# R2R_v2_1.net
KiCad netlist of a schematic drawn in EAGLE
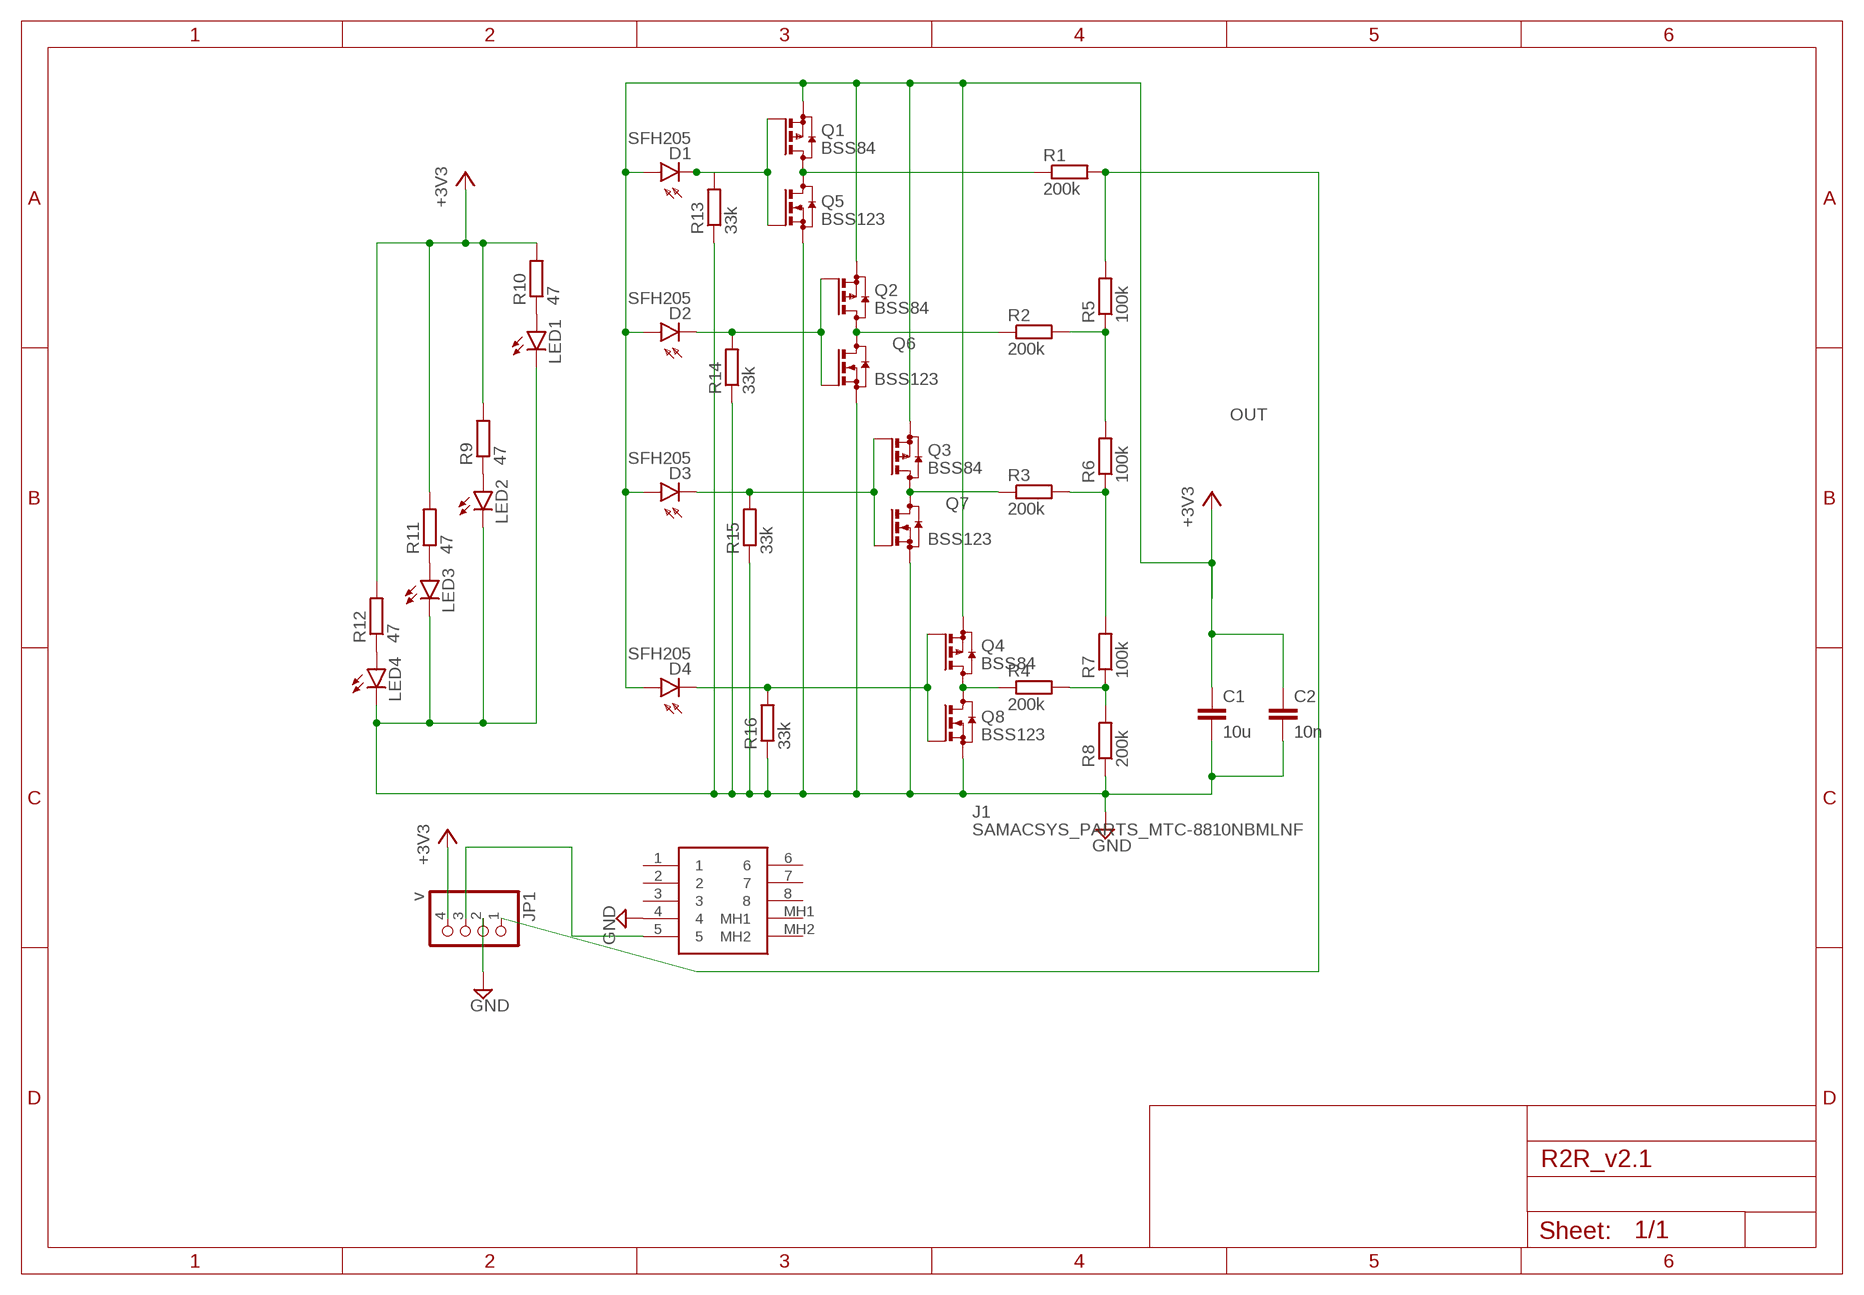
[diagram p0: schematic, sheet 1]

(export (version "E")
  (design (tool "Eeschema 10.0.6"))
  (components
    (comp (ref "C1")
      (value "10u")
      (footprint "eagle-import:C0805")
      (libsource (lib "eagle-import") (part "C-EUC0805"))
    )
    (comp (ref "C2")
      (value "10n")
      (footprint "eagle-import:C0805")
      (libsource (lib "eagle-import") (part "C-EUC0805"))
    )
    (comp (ref "D1")
      (value "SFH205")
      (footprint "eagle-import:SFH205")
      (libsource (lib "eagle-import") (part "SFH205"))
    )
    (comp (ref "D2")
      (value "SFH205")
      (footprint "eagle-import:SFH205")
      (libsource (lib "eagle-import") (part "SFH205"))
    )
    (comp (ref "D3")
      (value "SFH205")
      (footprint "eagle-import:SFH205")
      (libsource (lib "eagle-import") (part "SFH205"))
    )
    (comp (ref "D4")
      (value "SFH205")
      (footprint "eagle-import:SFH205")
      (libsource (lib "eagle-import") (part "SFH205"))
    )
    (comp (ref "J1")
      (value "SAMACSYS_PARTS_MTC-8810NBMLNF")
      (footprint "eagle-import:SAMACSYS_PARTS_MTC8810NBMLNF")
      (fields (field (name "MANUFACTURER_PART_NUMBER") "MTC-8810NBMLNF"))
      (libsource (lib "eagle-import") (part "SAMACSYS_PARTS_MTC-8810NBMLNF"))
    )
    (comp (ref "JP1")
      (value "v")
      (footprint "eagle-import:1X04")
      (libsource (lib "eagle-import") (part "PINHD-1X4"))
    )
    (comp (ref "LED1")
      (value "LED3MM")
      (footprint "eagle-import:LED3MM")
      (libsource (lib "eagle-import") (part "LED3MM"))
    )
    (comp (ref "LED2")
      (value "LED3MM")
      (footprint "eagle-import:LED3MM")
      (libsource (lib "eagle-import") (part "LED3MM"))
    )
    (comp (ref "LED3")
      (value "LED3MM")
      (footprint "eagle-import:LED3MM")
      (libsource (lib "eagle-import") (part "LED3MM"))
    )
    (comp (ref "LED4")
      (value "LED3MM")
      (footprint "eagle-import:LED3MM")
      (libsource (lib "eagle-import") (part "LED3MM"))
    )
    (comp (ref "Q1")
      (value "BSS84")
      (footprint "eagle-import:SOT23")
      (libsource (lib "eagle-import") (part "BSS84"))
    )
    (comp (ref "Q2")
      (value "BSS84")
      (footprint "eagle-import:SOT23")
      (libsource (lib "eagle-import") (part "BSS84"))
    )
    (comp (ref "Q3")
      (value "BSS84")
      (footprint "eagle-import:SOT23")
      (libsource (lib "eagle-import") (part "BSS84"))
    )
    (comp (ref "Q4")
      (value "BSS84")
      (footprint "eagle-import:SOT23")
      (libsource (lib "eagle-import") (part "BSS84"))
    )
    (comp (ref "Q5")
      (value "BSS123")
      (footprint "eagle-import:SOT23")
      (libsource (lib "eagle-import") (part "BSS123"))
    )
    (comp (ref "Q6")
      (value "BSS123")
      (footprint "eagle-import:SOT23")
      (libsource (lib "eagle-import") (part "BSS123"))
    )
    (comp (ref "Q7")
      (value "BSS123")
      (footprint "eagle-import:SOT23")
      (libsource (lib "eagle-import") (part "BSS123"))
    )
    (comp (ref "Q8")
      (value "BSS123")
      (footprint "eagle-import:SOT23")
      (libsource (lib "eagle-import") (part "BSS123"))
    )
    (comp (ref "R1")
      (value "200k")
      (footprint "eagle-import:R1206")
      (libsource (lib "eagle-import") (part "R-EU_R1206"))
    )
    (comp (ref "R2")
      (value "200k")
      (footprint "eagle-import:R1206")
      (libsource (lib "eagle-import") (part "R-EU_R1206"))
    )
    (comp (ref "R3")
      (value "200k")
      (footprint "eagle-import:R1206")
      (libsource (lib "eagle-import") (part "R-EU_R1206"))
    )
    (comp (ref "R4")
      (value "200k")
      (footprint "eagle-import:R1206")
      (libsource (lib "eagle-import") (part "R-EU_R1206"))
    )
    (comp (ref "R5")
      (value "100k")
      (footprint "eagle-import:R1206")
      (libsource (lib "eagle-import") (part "R-EU_R1206"))
    )
    (comp (ref "R6")
      (value "100k")
      (footprint "eagle-import:R1206")
      (libsource (lib "eagle-import") (part "R-EU_R1206"))
    )
    (comp (ref "R7")
      (value "100k")
      (footprint "eagle-import:R1206")
      (libsource (lib "eagle-import") (part "R-EU_R1206"))
    )
    (comp (ref "R8")
      (value "200k")
      (footprint "eagle-import:R1206")
      (libsource (lib "eagle-import") (part "R-EU_R1206"))
    )
    (comp (ref "R9")
      (value "47")
      (footprint "eagle-import:R1206")
      (libsource (lib "eagle-import") (part "R-EU_R1206"))
    )
    (comp (ref "R10")
      (value "47")
      (footprint "eagle-import:R1206")
      (libsource (lib "eagle-import") (part "R-EU_R1206"))
    )
    (comp (ref "R11")
      (value "47")
      (footprint "eagle-import:R1206")
      (libsource (lib "eagle-import") (part "R-EU_R1206"))
    )
    (comp (ref "R12")
      (value "47")
      (footprint "eagle-import:R1206")
      (libsource (lib "eagle-import") (part "R-EU_R1206"))
    )
    (comp (ref "R13")
      (value "33k")
      (footprint "eagle-import:R1206")
      (libsource (lib "eagle-import") (part "R-EU_R1206"))
    )
    (comp (ref "R14")
      (value "33k")
      (footprint "eagle-import:R1206")
      (libsource (lib "eagle-import") (part "R-EU_R1206"))
    )
    (comp (ref "R15")
      (value "33k")
      (footprint "eagle-import:R1206")
      (libsource (lib "eagle-import") (part "R-EU_R1206"))
    )
    (comp (ref "R16")
      (value "33k")
      (footprint "eagle-import:R1206")
      (libsource (lib "eagle-import") (part "R-EU_R1206"))
    )
  )
  (nets
    (net (code "1") (name "+3V3") (class "Default")
      (node (ref "C1") (pin "1") (pinfunction "1_1") (pintype "passive"))
      (node (ref "C2") (pin "1") (pinfunction "1_1") (pintype "passive"))
      (node (ref "D1") (pin "A") (pinfunction "A_A") (pintype "passive"))
      (node (ref "D2") (pin "A") (pinfunction "A_A") (pintype "passive"))
      (node (ref "D3") (pin "A") (pinfunction "A_A") (pintype "passive"))
      (node (ref "D4") (pin "A") (pinfunction "A_A") (pintype "passive"))
      (node (ref "JP1") (pin "4") (pinfunction "4_4") (pintype "passive"))
      (node (ref "Q1") (pin "2") (pinfunction "S_2") (pintype "passive"))
      (node (ref "Q2") (pin "2") (pinfunction "S_2") (pintype "passive"))
      (node (ref "Q3") (pin "2") (pinfunction "S_2") (pintype "passive"))
      (node (ref "Q4") (pin "2") (pinfunction "S_2") (pintype "passive"))
      (node (ref "R10") (pin "2") (pinfunction "2_2") (pintype "passive"))
      (node (ref "R11") (pin "2") (pinfunction "2_2") (pintype "passive"))
      (node (ref "R12") (pin "2") (pinfunction "2_2") (pintype "passive"))
      (node (ref "R9") (pin "2") (pinfunction "2_2") (pintype "passive"))
    )
    (net (code "2") (name "/OUT") (class "Default")
      (node (ref "JP1") (pin "1") (pinfunction "1_1") (pintype "passive"))
      (node (ref "R1") (pin "2") (pinfunction "2_2") (pintype "passive"))
      (node (ref "R5") (pin "2") (pinfunction "2_2") (pintype "passive"))
    )
    (net (code "3") (name "GND") (class "Default")
      (node (ref "C1") (pin "2") (pinfunction "2_2") (pintype "passive"))
      (node (ref "C2") (pin "2") (pinfunction "2_2") (pintype "passive"))
      (node (ref "J1") (pin "4") (pinfunction "4_4") (pintype "bidirectional"))
      (node (ref "JP1") (pin "2") (pinfunction "2_2") (pintype "passive"))
      (node (ref "LED1") (pin "K") (pinfunction "C_K") (pintype "passive"))
      (node (ref "LED2") (pin "K") (pinfunction "C_K") (pintype "passive"))
      (node (ref "LED3") (pin "K") (pinfunction "C_K") (pintype "passive"))
      (node (ref "LED4") (pin "K") (pinfunction "C_K") (pintype "passive"))
      (node (ref "Q5") (pin "2") (pinfunction "S_2") (pintype "passive"))
      (node (ref "Q6") (pin "2") (pinfunction "S_2") (pintype "passive"))
      (node (ref "Q7") (pin "2") (pinfunction "S_2") (pintype "passive"))
      (node (ref "Q8") (pin "2") (pinfunction "S_2") (pintype "passive"))
      (node (ref "R13") (pin "1") (pinfunction "1_1") (pintype "passive"))
      (node (ref "R14") (pin "1") (pinfunction "1_1") (pintype "passive"))
      (node (ref "R15") (pin "1") (pinfunction "1_1") (pintype "passive"))
      (node (ref "R16") (pin "1") (pinfunction "1_1") (pintype "passive"))
      (node (ref "R8") (pin "1") (pinfunction "1_1") (pintype "passive"))
    )
    (net (code "4") (name "Net-(D1-C)") (class "Default")
      (node (ref "D1") (pin "K") (pinfunction "C_K") (pintype "passive"))
      (node (ref "Q1") (pin "1") (pinfunction "G_1") (pintype "passive"))
      (node (ref "Q5") (pin "1") (pinfunction "G_1") (pintype "passive"))
      (node (ref "R13") (pin "2") (pinfunction "2_2") (pintype "passive"))
    )
    (net (code "5") (name "Net-(D2-C)") (class "Default")
      (node (ref "D2") (pin "K") (pinfunction "C_K") (pintype "passive"))
      (node (ref "Q2") (pin "1") (pinfunction "G_1") (pintype "passive"))
      (node (ref "Q6") (pin "1") (pinfunction "G_1") (pintype "passive"))
      (node (ref "R14") (pin "2") (pinfunction "2_2") (pintype "passive"))
    )
    (net (code "6") (name "Net-(D3-C)") (class "Default")
      (node (ref "D3") (pin "K") (pinfunction "C_K") (pintype "passive"))
      (node (ref "Q3") (pin "1") (pinfunction "G_1") (pintype "passive"))
      (node (ref "Q7") (pin "1") (pinfunction "G_1") (pintype "passive"))
      (node (ref "R15") (pin "2") (pinfunction "2_2") (pintype "passive"))
    )
    (net (code "7") (name "Net-(D4-C)") (class "Default")
      (node (ref "D4") (pin "K") (pinfunction "C_K") (pintype "passive"))
      (node (ref "Q4") (pin "1") (pinfunction "G_1") (pintype "passive"))
      (node (ref "Q8") (pin "1") (pinfunction "G_1") (pintype "passive"))
      (node (ref "R16") (pin "2") (pinfunction "2_2") (pintype "passive"))
    )
    (net (code "8") (name "Net-(J1-Pad5)") (class "Default")
      (node (ref "J1") (pin "5") (pinfunction "5_5") (pintype "bidirectional"))
      (node (ref "JP1") (pin "3") (pinfunction "3_3") (pintype "passive"))
    )
    (net (code "9") (name "Net-(LED1-PadA)") (class "Default")
      (node (ref "LED1") (pin "A") (pinfunction "A_A") (pintype "passive"))
      (node (ref "R10") (pin "1") (pinfunction "1_1") (pintype "passive"))
    )
    (net (code "10") (name "Net-(LED2-PadA)") (class "Default")
      (node (ref "LED2") (pin "A") (pinfunction "A_A") (pintype "passive"))
      (node (ref "R9") (pin "1") (pinfunction "1_1") (pintype "passive"))
    )
    (net (code "11") (name "Net-(LED3-PadA)") (class "Default")
      (node (ref "LED3") (pin "A") (pinfunction "A_A") (pintype "passive"))
      (node (ref "R11") (pin "1") (pinfunction "1_1") (pintype "passive"))
    )
    (net (code "12") (name "Net-(LED4-PadA)") (class "Default")
      (node (ref "LED4") (pin "A") (pinfunction "A_A") (pintype "passive"))
      (node (ref "R12") (pin "1") (pinfunction "1_1") (pintype "passive"))
    )
    (net (code "13") (name "Net-(Q1-D)") (class "Default")
      (node (ref "Q1") (pin "3") (pinfunction "D_3") (pintype "passive"))
      (node (ref "Q5") (pin "3") (pinfunction "D_3") (pintype "passive"))
      (node (ref "R1") (pin "1") (pinfunction "1_1") (pintype "passive"))
    )
    (net (code "14") (name "Net-(Q2-D)") (class "Default")
      (node (ref "Q2") (pin "3") (pinfunction "D_3") (pintype "passive"))
      (node (ref "Q6") (pin "3") (pinfunction "D_3") (pintype "passive"))
      (node (ref "R2") (pin "1") (pinfunction "1_1") (pintype "passive"))
    )
    (net (code "15") (name "Net-(Q3-D)") (class "Default")
      (node (ref "Q3") (pin "3") (pinfunction "D_3") (pintype "passive"))
      (node (ref "Q7") (pin "3") (pinfunction "D_3") (pintype "passive"))
      (node (ref "R3") (pin "1") (pinfunction "1_1") (pintype "passive"))
    )
    (net (code "16") (name "Net-(Q4-D)") (class "Default")
      (node (ref "Q4") (pin "3") (pinfunction "D_3") (pintype "passive"))
      (node (ref "Q8") (pin "3") (pinfunction "D_3") (pintype "passive"))
      (node (ref "R4") (pin "1") (pinfunction "1_1") (pintype "passive"))
    )
    (net (code "17") (name "Net-(R2-Pad2)") (class "Default")
      (node (ref "R2") (pin "2") (pinfunction "2_2") (pintype "passive"))
      (node (ref "R5") (pin "1") (pinfunction "1_1") (pintype "passive"))
      (node (ref "R6") (pin "2") (pinfunction "2_2") (pintype "passive"))
    )
    (net (code "18") (name "Net-(R3-Pad2)") (class "Default")
      (node (ref "R3") (pin "2") (pinfunction "2_2") (pintype "passive"))
      (node (ref "R6") (pin "1") (pinfunction "1_1") (pintype "passive"))
      (node (ref "R7") (pin "2") (pinfunction "2_2") (pintype "passive"))
    )
    (net (code "19") (name "Net-(R4-Pad2)") (class "Default")
      (node (ref "R4") (pin "2") (pinfunction "2_2") (pintype "passive"))
      (node (ref "R7") (pin "1") (pinfunction "1_1") (pintype "passive"))
      (node (ref "R8") (pin "2") (pinfunction "2_2") (pintype "passive"))
    )
    (net (code "20") (name "unconnected-(J1-Pad1)") (class "Default")
      (node (ref "J1") (pin "1") (pinfunction "1_1") (pintype "bidirectional"))
    )
    (net (code "21") (name "unconnected-(J1-Pad2)") (class "Default")
      (node (ref "J1") (pin "2") (pinfunction "2_2") (pintype "bidirectional"))
    )
    (net (code "22") (name "unconnected-(J1-Pad3)") (class "Default")
      (node (ref "J1") (pin "3") (pinfunction "3_3") (pintype "bidirectional"))
    )
    (net (code "23") (name "unconnected-(J1-Pad6)") (class "Default")
      (node (ref "J1") (pin "6") (pinfunction "6_6") (pintype "bidirectional"))
    )
    (net (code "24") (name "unconnected-(J1-Pad7)") (class "Default")
      (node (ref "J1") (pin "7") (pinfunction "7_7") (pintype "bidirectional"))
    )
    (net (code "25") (name "unconnected-(J1-Pad8)") (class "Default")
      (node (ref "J1") (pin "8") (pinfunction "8_8") (pintype "bidirectional"))
    )
    (net (code "26") (name "unconnected-(J1-PadMH1)") (class "Default")
      (node (ref "J1") (pin "MH1") (pinfunction "MH1_MH1") (pintype "bidirectional"))
    )
    (net (code "27") (name "unconnected-(J1-PadMH2)") (class "Default")
      (node (ref "J1") (pin "MH2") (pinfunction "MH2_MH2") (pintype "bidirectional"))
    )
  )
)
